# ReSpeaker_Mic_SMD20_V04.net
KiCad netlist of a schematic drawn in EAGLE
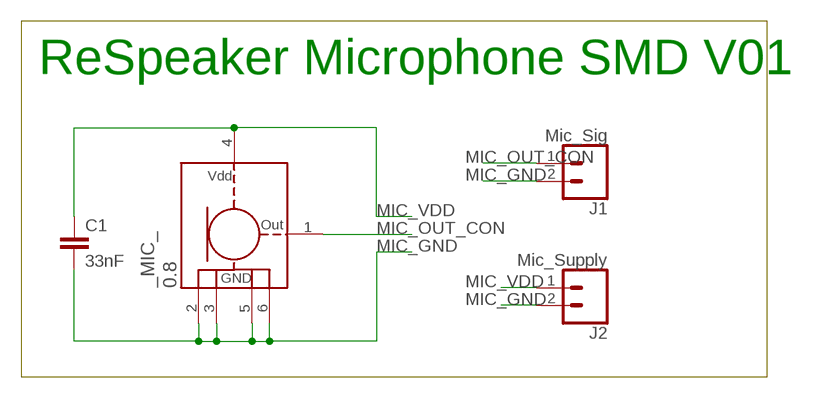
[diagram p0: schematic, sheet 1]

(export (version "E")
  (design (tool "Eeschema 10.0.6"))
  (components
    (comp (ref "C1")
      (value "33nF")
      (footprint "eagle-import:0805")
      (libsource (lib "eagle-import") (part "1.0UF-0805-25V-10%"))
    )
    (comp (ref "J1")
      (value "Mic_Sig")
      (footprint "eagle-import:1X02_2.0MM")
      (libsource (lib "eagle-import") (part "CONN_021X02_2MM"))
    )
    (comp (ref "J2")
      (value "Mic_Supply")
      (footprint "eagle-import:1X02_2.0MM")
      (libsource (lib "eagle-import") (part "CONN_021X02_2MM"))
    )
    (comp (ref "_MIC_")
      (value "0.8")
      (footprint "eagle-import:SPU0410LR5H-QB_0.8")
      (libsource (lib "eagle-import") (part "SPU0410LR5H-QBSPU0410LR5H-QB_0.8"))
    )
  )
  (nets
    (net (code "1") (name "/MIC_GND") (class "Default")
      (node (ref "C1") (pin "2") (pinfunction "2_2") (pintype "passive"))
      (node (ref "J1") (pin "2") (pinfunction "2_2") (pintype "passive"))
      (node (ref "J2") (pin "2") (pinfunction "2_2") (pintype "passive"))
      (node (ref "_MIC_") (pin "2") (pinfunction "GND_2") (pintype "bidirectional"))
      (node (ref "_MIC_") (pin "3") (pinfunction "GND_3") (pintype "bidirectional"))
      (node (ref "_MIC_") (pin "5") (pinfunction "GND_5") (pintype "bidirectional"))
      (node (ref "_MIC_") (pin "6") (pinfunction "GND_6") (pintype "bidirectional"))
    )
    (net (code "2") (name "/MIC_OUT_CON") (class "Default")
      (node (ref "J1") (pin "1") (pinfunction "1_1") (pintype "passive"))
      (node (ref "_MIC_") (pin "1") (pinfunction "OUT_1") (pintype "bidirectional"))
    )
    (net (code "3") (name "/MIC_VDD") (class "Default")
      (node (ref "C1") (pin "1") (pinfunction "1_1") (pintype "passive"))
      (node (ref "J2") (pin "1") (pinfunction "1_1") (pintype "passive"))
      (node (ref "_MIC_") (pin "4") (pinfunction "VDD_4") (pintype "bidirectional"))
    )
  )
)
